# power_layout.net
KiCad netlist of a schematic drawn in EAGLE
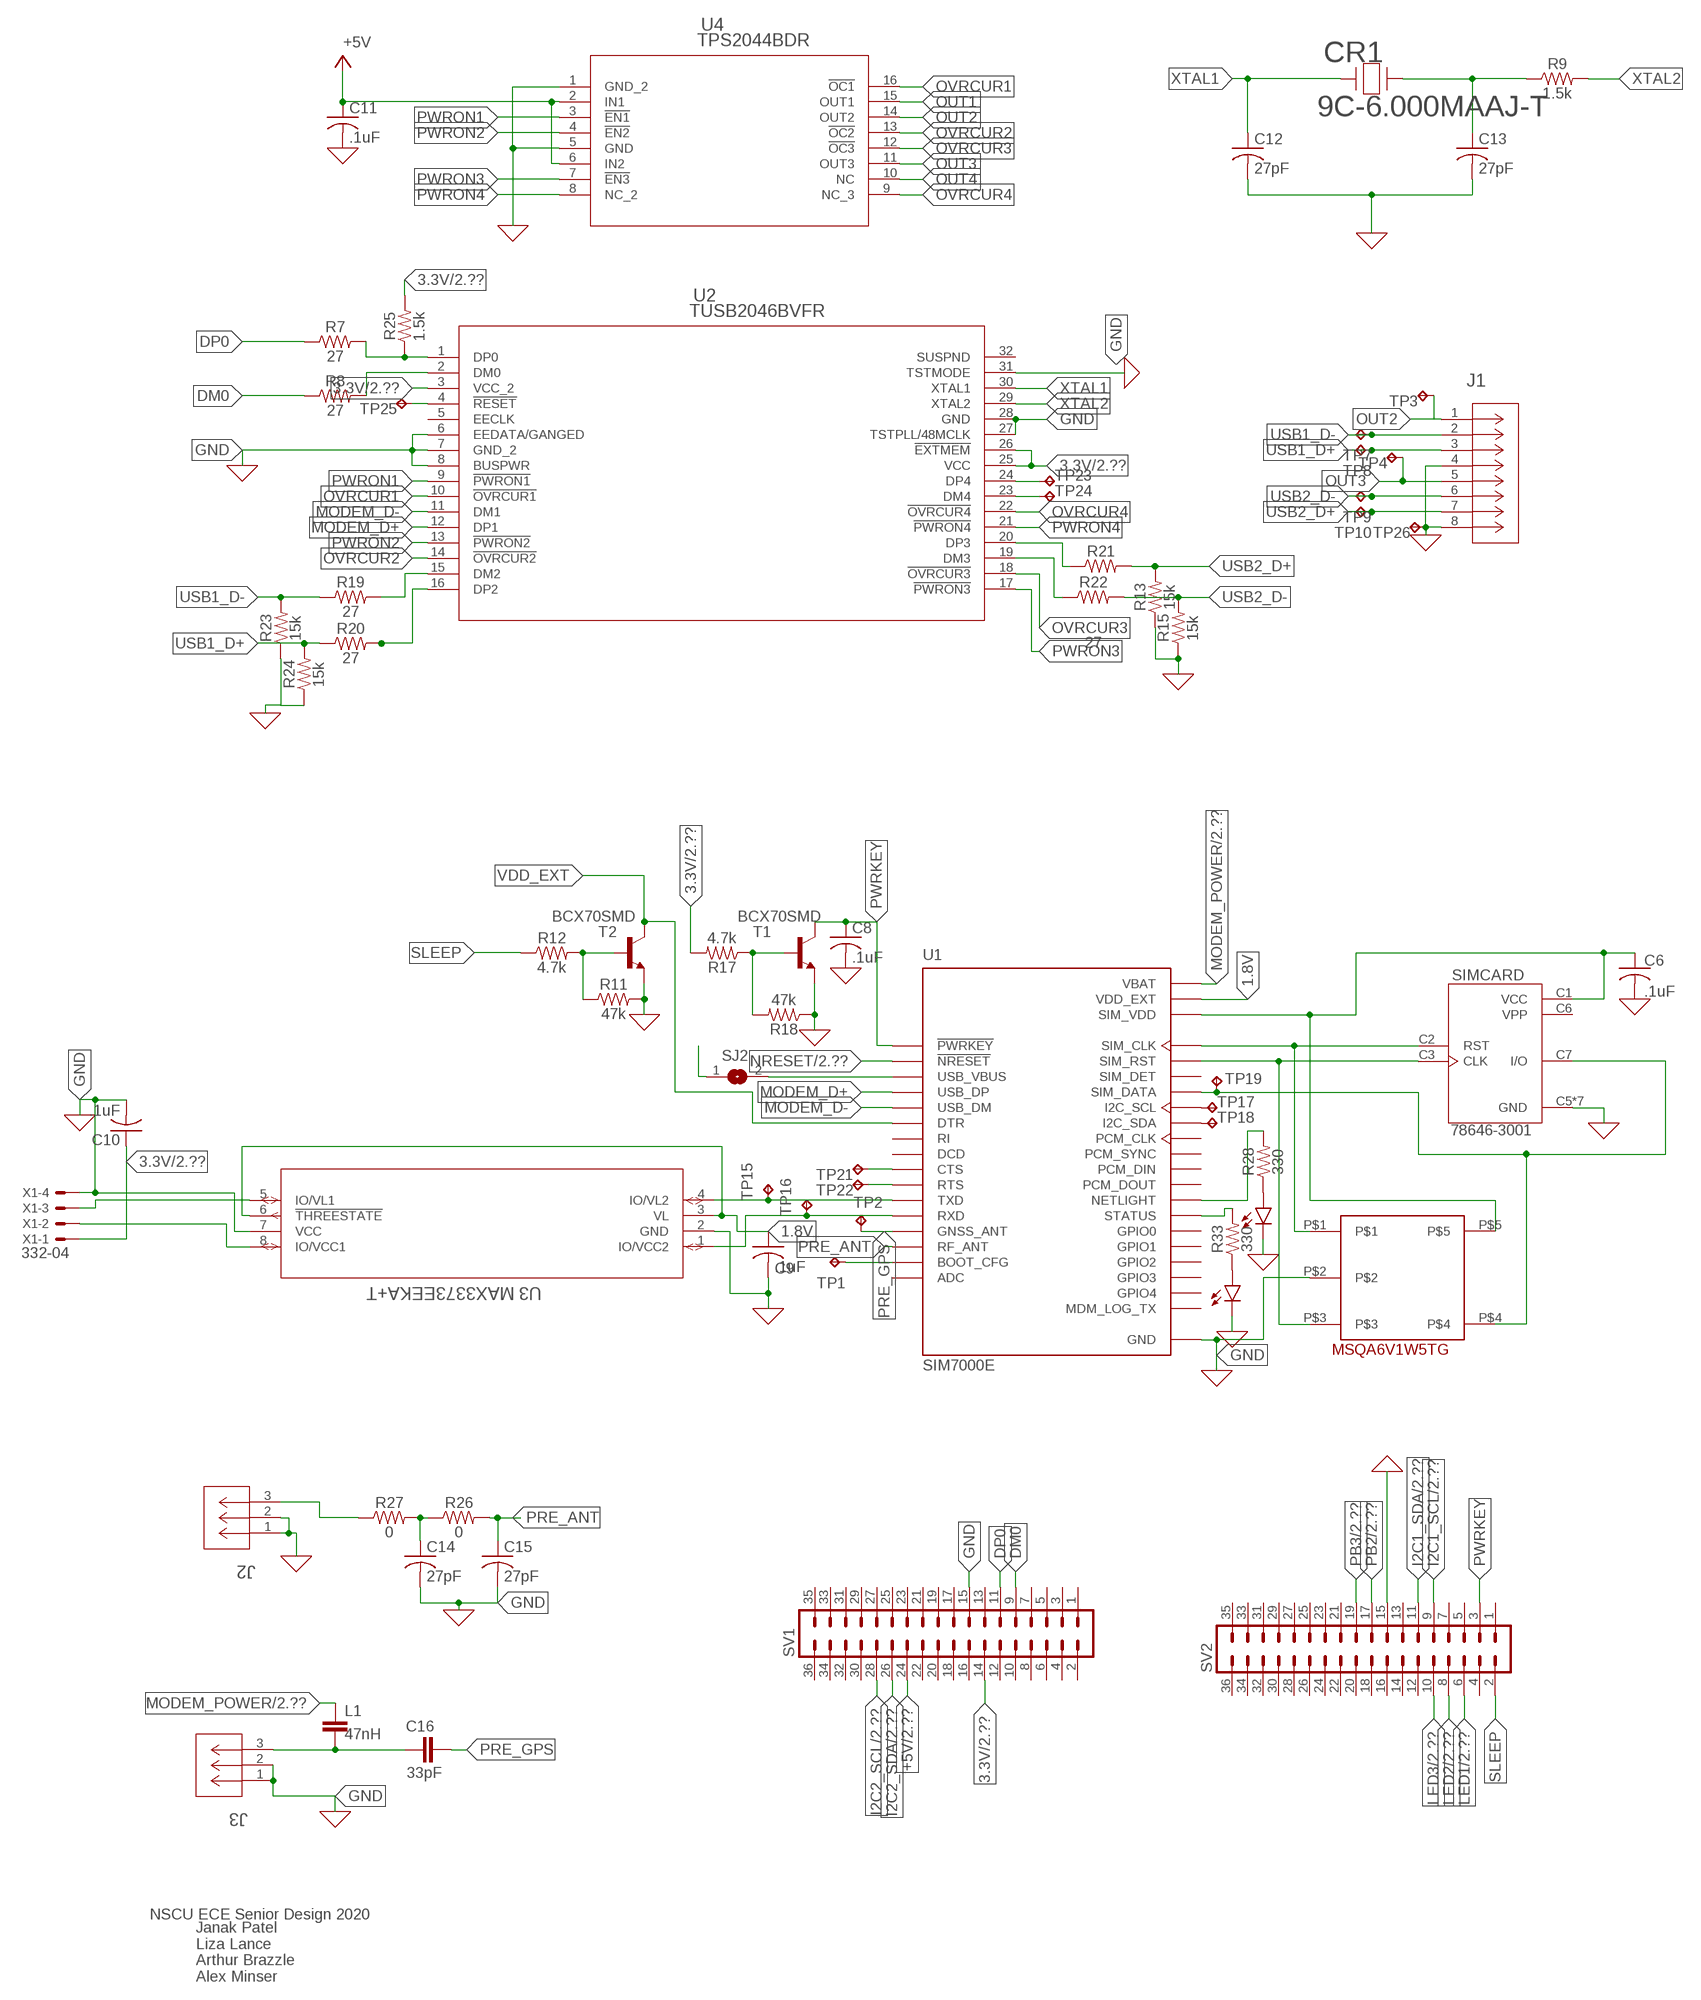
[diagram p0: schematic, sheet 1]
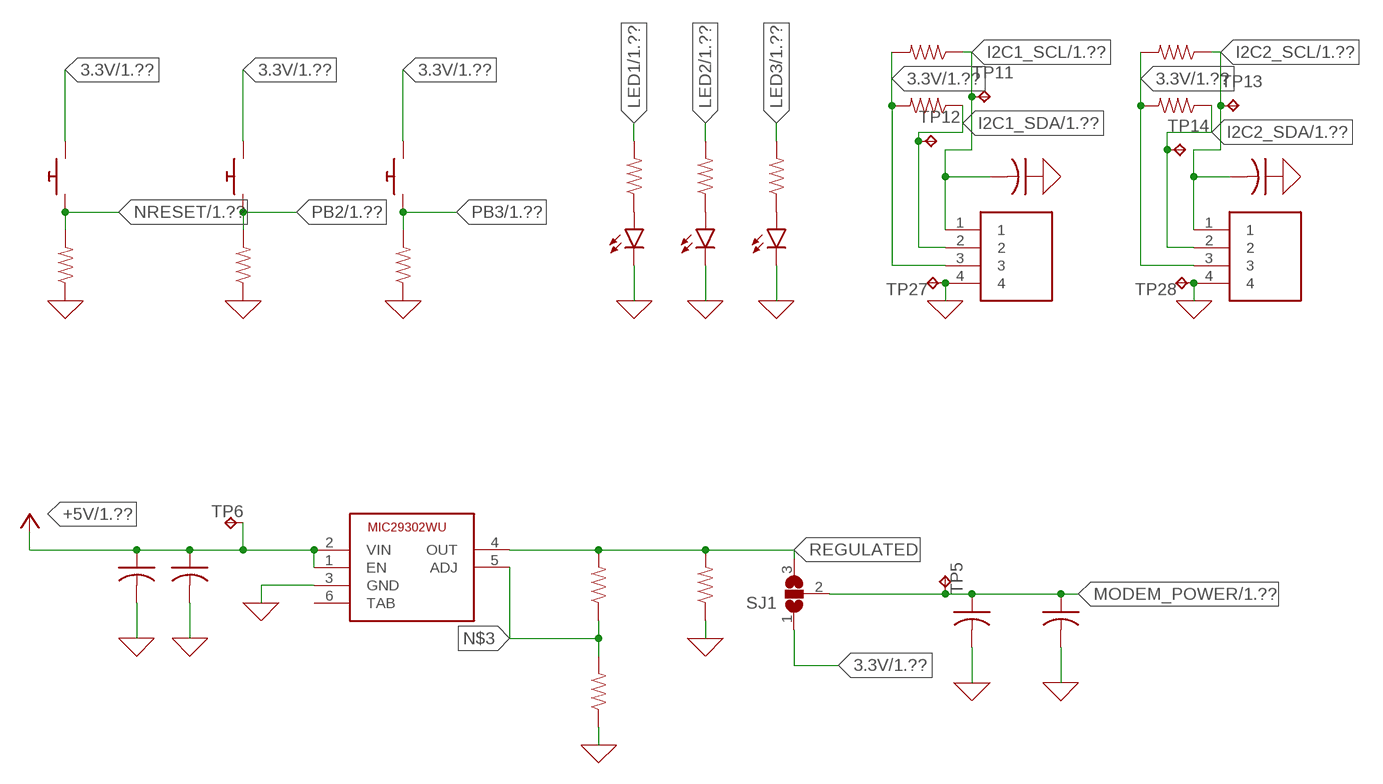
[diagram p1: schematic, sheet 2]

(export (version "E")
  (design (tool "Eeschema 10.0.6"))
  (components
    (comp (ref "C1")
      (value "100uF")
      (footprint "eagle-import:C0805")
      (libsource (lib "eagle-import") (part "C-USC0805"))
    )
    (comp (ref "C2")
      (value "0.1uF")
      (footprint "eagle-import:C0805")
      (libsource (lib "eagle-import") (part "C-USC0805"))
    )
    (comp (ref "C3")
      (value "330uF")
      (footprint "eagle-import:C1210")
      (libsource (lib "eagle-import") (part "C-USC1210"))
    )
    (comp (ref "C4")
      (value "1uF")
      (footprint "eagle-import:C0805")
      (libsource (lib "eagle-import") (part "C-USC0805"))
    )
    (comp (ref "C5")
      (value "100nF")
      (footprint "eagle-import:C0805")
      (libsource (lib "eagle-import") (part "C-USC0805"))
    )
    (comp (ref "C7")
      (value "0.1uF")
      (footprint "eagle-import:C0805")
      (libsource (lib "eagle-import") (part "C-USC0805"))
    )
    (comp (ref "D1")
      (value "RED")
      (footprint "eagle-import:LED-1206")
      (libsource (lib "eagle-import") (part "LED-RED1206"))
    )
    (comp (ref "D2")
      (value "GREEN")
      (footprint "eagle-import:LED-1206")
      (libsource (lib "eagle-import") (part "LED-GREEN1206"))
    )
    (comp (ref "D3")
      (value "BLUE")
      (footprint "eagle-import:LED-1206")
      (libsource (lib "eagle-import") (part "LED-BLUE1206"))
    )
    (comp (ref "GROVE1")
      (value "640456-4")
      (footprint "eagle-import:TE_640456-4")
      (fields (field (name "DIGI-KEY_PART_NUMBER") "A1922-ND") (field (name "MF") "TE Connectivity"))
      (libsource (lib "eagle-import") (part "640456-4"))
    )
    (comp (ref "GROVE2")
      (value "640456-4")
      (footprint "eagle-import:TE_640456-4")
      (fields (field (name "DIGI-KEY_PART_NUMBER") "A1922-ND") (field (name "MF") "TE Connectivity"))
      (libsource (lib "eagle-import") (part "640456-4"))
    )
    (comp (ref "POWER_SUPPLY")
      (value "MIC29302WU")
      (footprint "eagle-import:TO263-5")
      (fields (field (name "MF") "Microchip Technology"))
      (libsource (lib "eagle-import") (part "MIC29302WU"))
    )
    (comp (ref "R1")
      (value "60.4")
      (footprint "eagle-import:0805")
      (libsource (lib "eagle-import") (part "RESISTOR0805"))
    )
    (comp (ref "R2")
      (value "180")
      (footprint "eagle-import:0805")
      (libsource (lib "eagle-import") (part "RESISTOR0805"))
    )
    (comp (ref "R3")
      (value "180")
      (footprint "eagle-import:0805")
      (libsource (lib "eagle-import") (part "RESISTOR0805"))
    )
    (comp (ref "R4")
      (value "47k")
      (footprint "eagle-import:0805")
      (libsource (lib "eagle-import") (part "RESISTOR0805"))
    )
    (comp (ref "R5")
      (value "100k")
      (footprint "eagle-import:0805")
      (libsource (lib "eagle-import") (part "RESISTOR0805"))
    )
    (comp (ref "R6")
      (value "470k")
      (footprint "eagle-import:0805")
      (libsource (lib "eagle-import") (part "RESISTOR0805"))
    )
    (comp (ref "R10")
      (value "4700")
      (footprint "eagle-import:0805")
      (libsource (lib "eagle-import") (part "RESISTOR0805"))
    )
    (comp (ref "R14")
      (value "4700")
      (footprint "eagle-import:0805")
      (libsource (lib "eagle-import") (part "RESISTOR0805"))
    )
    (comp (ref "R16")
      (value "4700")
      (footprint "eagle-import:0805")
      (libsource (lib "eagle-import") (part "RESISTOR0805"))
    )
    (comp (ref "R29")
      (value "4700")
      (footprint "eagle-import:0805")
      (libsource (lib "eagle-import") (part "RESISTOR0805"))
    )
    (comp (ref "R30")
      (value "4700")
      (footprint "eagle-import:0805")
      (libsource (lib "eagle-import") (part "RESISTOR0805"))
    )
    (comp (ref "R31")
      (value "4700")
      (footprint "eagle-import:0805")
      (libsource (lib "eagle-import") (part "RESISTOR0805"))
    )
    (comp (ref "R32")
      (value "4700")
      (footprint "eagle-import:0805")
      (libsource (lib "eagle-import") (part "RESISTOR0805"))
    )
    (comp (ref "SJ1")
      (value "SJ2W")
      (footprint "eagle-import:SJ_2")
      (libsource (lib "eagle-import") (part "SJ2W"))
    )
    (comp (ref "SW1")
      (value "SWITCH_PUSHBUTTONSOFTTOUCHSMD_SJ")
      (footprint "eagle-import:PUSHBUTTON_SMD_SJ")
      (libsource (lib "eagle-import") (part "SWITCH_PUSHBUTTONSOFTTOUCHSMD_SJ"))
    )
    (comp (ref "SW2")
      (value "SWITCH_PUSHBUTTONSOFTTOUCHSMD_SJ")
      (footprint "eagle-import:PUSHBUTTON_SMD_SJ")
      (libsource (lib "eagle-import") (part "SWITCH_PUSHBUTTONSOFTTOUCHSMD_SJ"))
    )
    (comp (ref "SW3")
      (value "SWITCH_PUSHBUTTONSOFTTOUCHSMD_SJ")
      (footprint "eagle-import:PUSHBUTTON_SMD_SJ")
      (libsource (lib "eagle-import") (part "SWITCH_PUSHBUTTONSOFTTOUCHSMD_SJ"))
    )
    (comp (ref "TP5")
      (value "TPTP10R")
      (footprint "eagle-import:TP10R")
      (libsource (lib "eagle-import") (part "TPTP10R"))
    )
    (comp (ref "TP6")
      (value "TPTP10R")
      (footprint "eagle-import:TP10R")
      (libsource (lib "eagle-import") (part "TPTP10R"))
    )
    (comp (ref "TP11")
      (value "TPTP10R")
      (footprint "eagle-import:TP10R")
      (libsource (lib "eagle-import") (part "TPTP10R"))
    )
    (comp (ref "TP12")
      (value "TPTP10R")
      (footprint "eagle-import:TP10R")
      (libsource (lib "eagle-import") (part "TPTP10R"))
    )
    (comp (ref "TP13")
      (value "TPTP10R")
      (footprint "eagle-import:TP10R")
      (libsource (lib "eagle-import") (part "TPTP10R"))
    )
    (comp (ref "TP14")
      (value "TPTP10R")
      (footprint "eagle-import:TP10R")
      (libsource (lib "eagle-import") (part "TPTP10R"))
    )
    (comp (ref "TP27")
      (value "TPTP10R")
      (footprint "eagle-import:TP10R")
      (libsource (lib "eagle-import") (part "TPTP10R"))
    )
    (comp (ref "TP28")
      (value "TPTP10R")
      (footprint "eagle-import:TP10R")
      (libsource (lib "eagle-import") (part "TPTP10R"))
    )
    (comp (ref "C6")
      (value ".1uF")
      (footprint "eagle-import:C0805")
      (libsource (lib "eagle-import") (part "C-USC0805"))
    )
    (comp (ref "C8")
      (value ".1uF")
      (footprint "eagle-import:C0805")
      (libsource (lib "eagle-import") (part "C-USC0805"))
    )
    (comp (ref "C9")
      (value ".1uF")
      (footprint "eagle-import:C0805")
      (libsource (lib "eagle-import") (part "C-USC0805"))
    )
    (comp (ref "C10")
      (value ".1uF")
      (footprint "eagle-import:C0805")
      (libsource (lib "eagle-import") (part "C-USC0805"))
    )
    (comp (ref "C11")
      (value ".1uF")
      (footprint "eagle-import:C0805")
      (libsource (lib "eagle-import") (part "C-USC0805"))
    )
    (comp (ref "C12")
      (value "27pF")
      (footprint "eagle-import:C0603")
      (libsource (lib "eagle-import") (part "C-USC0603"))
    )
    (comp (ref "C13")
      (value "27pF")
      (footprint "eagle-import:C0603")
      (libsource (lib "eagle-import") (part "C-USC0603"))
    )
    (comp (ref "C14")
      (value "27pF")
      (footprint "eagle-import:C0603")
      (libsource (lib "eagle-import") (part "C-USC0603"))
    )
    (comp (ref "C15")
      (value "27pF")
      (footprint "eagle-import:C0603")
      (libsource (lib "eagle-import") (part "C-USC0603"))
    )
    (comp (ref "C16")
      (value "33pF")
      (footprint "eagle-import:C0603K")
      (libsource (lib "eagle-import") (part "C-EUC0603K"))
    )
    (comp (ref "CR1")
      (value "9C-6.000MAAJ-T")
      (footprint "eagle-import:CRYSTAL_TXC_9C_TXC")
      (libsource (lib "eagle-import") (part "9C-6.000MAAJ-T"))
    )
    (comp (ref "D4")
      (value "Yellow")
      (footprint "eagle-import:LED-0603")
      (libsource (lib "eagle-import") (part "LED-YELLOW0603"))
    )
    (comp (ref "D5")
      (value "Yellow")
      (footprint "eagle-import:LED-0603")
      (libsource (lib "eagle-import") (part "LED-YELLOW0603"))
    )
    (comp (ref "J1")
      (value "AU-Y1008-2")
      (footprint "eagle-import:CONN_AU-Y1008-2_ASM")
      (fields (field (name "COPYRIGHT") "Copyright (C) 2018 Accelerated Designs. All rights reserved"))
      (libsource (lib "eagle-import") (part "AU-Y1008-2"))
    )
    (comp (ref "J2")
      (value "U.FL-R-SMT-1(01)")
      (footprint "eagle-import:CONN_-SMT-1(01)")
      (fields (field (name "COPYRIGHT") "Copyright (C) 2018 Accelerated Designs. All rights reserved"))
      (libsource (lib "eagle-import") (part "U.FL-R-SMT-1(01)"))
    )
    (comp (ref "J3")
      (value "U.FL-R-SMT-1(01)")
      (footprint "eagle-import:CONN_-SMT-1(01)")
      (fields (field (name "COPYRIGHT") "Copyright (C) 2018 Accelerated Designs. All rights reserved"))
      (libsource (lib "eagle-import") (part "U.FL-R-SMT-1(01)"))
    )
    (comp (ref "L1")
      (value "47nH")
      (footprint "eagle-import:C1608")
      (libsource (lib "eagle-import") (part "C-EUC1608"))
    )
    (comp (ref "R7")
      (value "27")
      (footprint "eagle-import:0805")
      (libsource (lib "eagle-import") (part "RESISTOR0805"))
    )
    (comp (ref "R8")
      (value "27")
      (footprint "eagle-import:0805")
      (libsource (lib "eagle-import") (part "RESISTOR0805"))
    )
    (comp (ref "R9")
      (value "1.5k")
      (footprint "eagle-import:0603")
      (libsource (lib "eagle-import") (part "1KOHM-0603-1/10W-1%"))
    )
    (comp (ref "R11")
      (value "47k")
      (footprint "eagle-import:0603")
      (libsource (lib "eagle-import") (part "47KOHM-0603-1/10W-1%"))
    )
    (comp (ref "R12")
      (value "4.7k")
      (footprint "eagle-import:0603")
      (libsource (lib "eagle-import") (part "4.7KOHM-0603-1/10W-1%"))
    )
    (comp (ref "R13")
      (value "15k")
      (footprint "eagle-import:0805")
      (libsource (lib "eagle-import") (part "RESISTOR0805"))
    )
    (comp (ref "R15")
      (value "15k")
      (footprint "eagle-import:0805")
      (libsource (lib "eagle-import") (part "RESISTOR0805"))
    )
    (comp (ref "R17")
      (value "4.7k")
      (footprint "eagle-import:0603")
      (libsource (lib "eagle-import") (part "4.7KOHM-0603-1/10W-1%"))
    )
    (comp (ref "R18")
      (value "47k")
      (footprint "eagle-import:0603")
      (libsource (lib "eagle-import") (part "47KOHM-0603-1/10W-1%"))
    )
    (comp (ref "R19")
      (value "27")
      (footprint "eagle-import:0805")
      (libsource (lib "eagle-import") (part "RESISTOR0805"))
    )
    (comp (ref "R20")
      (value "27")
      (footprint "eagle-import:0805")
      (libsource (lib "eagle-import") (part "RESISTOR0805"))
    )
    (comp (ref "R21")
      (value "27")
      (footprint "eagle-import:0805")
      (libsource (lib "eagle-import") (part "RESISTOR0805"))
    )
    (comp (ref "R22")
      (value "27")
      (footprint "eagle-import:0805")
      (libsource (lib "eagle-import") (part "RESISTOR0805"))
    )
    (comp (ref "R23")
      (value "15k")
      (footprint "eagle-import:0805")
      (libsource (lib "eagle-import") (part "RESISTOR0805"))
    )
    (comp (ref "R24")
      (value "15k")
      (footprint "eagle-import:0805")
      (libsource (lib "eagle-import") (part "RESISTOR0805"))
    )
    (comp (ref "R25")
      (value "1.5k")
      (footprint "eagle-import:0805")
      (libsource (lib "eagle-import") (part "RESISTOR0805"))
    )
    (comp (ref "R26")
      (value "0")
      (footprint "eagle-import:0603")
      (libsource (lib "eagle-import") (part "1KOHM-0603-1/10W-1%"))
    )
    (comp (ref "R27")
      (value "0")
      (footprint "eagle-import:0603")
      (libsource (lib "eagle-import") (part "1KOHM-0603-1/10W-1%"))
    )
    (comp (ref "R28")
      (value "330")
      (footprint "eagle-import:0603")
      (libsource (lib "eagle-import") (part "1KOHM-0603-1/10W-1%"))
    )
    (comp (ref "R33")
      (value "330")
      (footprint "eagle-import:0603")
      (libsource (lib "eagle-import") (part "1KOHM-0603-1/10W-1%"))
    )
    (comp (ref "SIMCARD")
      (value "78646-3001")
      (footprint "eagle-import:MOLEX_78646-3001")
      (fields (field (name "MF") "Molex"))
      (libsource (lib "eagle-import") (part "78646-3001"))
    )
    (comp (ref "SJ2") (value "SJ") (footprint "eagle-import:SJ") (libsource (lib "eagle-import") (part "SJ")))
    (comp (ref "SV1")
      (value "MA18-2")
      (footprint "eagle-import:MA18-2")
      (libsource (lib "eagle-import") (part "MA18-2"))
    )
    (comp (ref "SV2")
      (value "MA18-2")
      (footprint "eagle-import:MA18-2")
      (libsource (lib "eagle-import") (part "MA18-2"))
    )
    (comp (ref "T1")
      (value "BCX70SMD")
      (footprint "eagle-import:SOT23")
      (libsource (lib "eagle-import") (part "BCX70SMD"))
    )
    (comp (ref "T2")
      (value "BCX70SMD")
      (footprint "eagle-import:SOT23")
      (libsource (lib "eagle-import") (part "BCX70SMD"))
    )
    (comp (ref "TP1")
      (value "TPTP10R")
      (footprint "eagle-import:TP10R")
      (libsource (lib "eagle-import") (part "TPTP10R"))
    )
    (comp (ref "TP2")
      (value "TPTP16R")
      (footprint "eagle-import:TP16R")
      (libsource (lib "eagle-import") (part "TPTP16R"))
    )
    (comp (ref "TP3")
      (value "TPTP10R")
      (footprint "eagle-import:TP10R")
      (libsource (lib "eagle-import") (part "TPTP10R"))
    )
    (comp (ref "TP4")
      (value "TPTP10R")
      (footprint "eagle-import:TP10R")
      (libsource (lib "eagle-import") (part "TPTP10R"))
    )
    (comp (ref "TP7")
      (value "TPTP10R")
      (footprint "eagle-import:TP10R")
      (libsource (lib "eagle-import") (part "TPTP10R"))
    )
    (comp (ref "TP8")
      (value "TPTP10R")
      (footprint "eagle-import:TP10R")
      (libsource (lib "eagle-import") (part "TPTP10R"))
    )
    (comp (ref "TP9")
      (value "TPTP10R")
      (footprint "eagle-import:TP10R")
      (libsource (lib "eagle-import") (part "TPTP10R"))
    )
    (comp (ref "TP10")
      (value "TPTP10R")
      (footprint "eagle-import:TP10R")
      (libsource (lib "eagle-import") (part "TPTP10R"))
    )
    (comp (ref "TP15")
      (value "TPTP10R")
      (footprint "eagle-import:TP10R")
      (libsource (lib "eagle-import") (part "TPTP10R"))
    )
    (comp (ref "TP16")
      (value "TPTP10R")
      (footprint "eagle-import:TP10R")
      (libsource (lib "eagle-import") (part "TPTP10R"))
    )
    (comp (ref "TP17")
      (value "TPTP10R")
      (footprint "eagle-import:TP10R")
      (libsource (lib "eagle-import") (part "TPTP10R"))
    )
    (comp (ref "TP18")
      (value "TPTP10R")
      (footprint "eagle-import:TP10R")
      (libsource (lib "eagle-import") (part "TPTP10R"))
    )
    (comp (ref "TP19")
      (value "TPTP10R")
      (footprint "eagle-import:TP10R")
      (libsource (lib "eagle-import") (part "TPTP10R"))
    )
    (comp (ref "TP21")
      (value "TPTP10R")
      (footprint "eagle-import:TP10R")
      (libsource (lib "eagle-import") (part "TPTP10R"))
    )
    (comp (ref "TP22")
      (value "TPTP10R")
      (footprint "eagle-import:TP10R")
      (libsource (lib "eagle-import") (part "TPTP10R"))
    )
    (comp (ref "TP23")
      (value "TPTP10R")
      (footprint "eagle-import:TP10R")
      (libsource (lib "eagle-import") (part "TPTP10R"))
    )
    (comp (ref "TP24")
      (value "TPTP10R")
      (footprint "eagle-import:TP10R")
      (libsource (lib "eagle-import") (part "TPTP10R"))
    )
    (comp (ref "TP25")
      (value "TPTP10R")
      (footprint "eagle-import:TP10R")
      (libsource (lib "eagle-import") (part "TPTP10R"))
    )
    (comp (ref "TP26")
      (value "TPTP10R")
      (footprint "eagle-import:TP10R")
      (libsource (lib "eagle-import") (part "TPTP10R"))
    )
    (comp (ref "U1")
      (value "SIM7000E")
      (footprint "eagle-import:SIMCON_SIM7000E")
      (fields (field (name "MF") "DFRobot"))
      (libsource (lib "eagle-import") (part "SIM7000E"))
    )
    (comp (ref "U2")
      (value "TUSB2046BVFR")
      (footprint "eagle-import:VF32_TEX")
      (fields
        (field (name "MANUFACTURER") "Texas Instruments")
        (field (name "COPYRIGHT") "Copyright (C) 2018 Accelerated Designs. All rights reserved")
      )
      (libsource (lib "eagle-import") (part "TUSB2046BVFR"))
    )
    (comp (ref "U3")
      (value "MAX3373EEKA+T")
      (footprint "eagle-import:21-0078H")
      (fields (field (name "MANUFACTURER_PART_NUMBER") "max3373eeka+t"))
      (libsource (lib "eagle-import") (part "MAX3373EEKA+T"))
    )
    (comp (ref "U4")
      (value "TPS2044BDR")
      (footprint "eagle-import:D16_TEX")
      (fields (field (name "MANUFACTURER") "Texas Instruments"))
      (libsource (lib "eagle-import") (part "TPS2044BDR"))
    )
    (comp (ref "U5")
      (value "MSQA6V1W5T2G")
      (footprint "eagle-import:SOT-23-5_M5")
      (libsource (lib "eagle-import") (part "MSQA6V1W5T2G"))
    )
    (comp (ref "X1")
      (value "332-04")
      (footprint "eagle-import:332-04")
      (libsource (lib "eagle-import") (part "332-04"))
    )
  )
  (nets
    (net (code "1") (name "+5V") (class "Default")
      (node (ref "C1") (pin "1") (pinfunction "1_1") (pintype "passive"))
      (node (ref "C11") (pin "1") (pinfunction "1_1") (pintype "passive"))
      (node (ref "C4") (pin "1") (pinfunction "1_1") (pintype "passive"))
      (node (ref "POWER_SUPPLY") (pin "1") (pinfunction "EN_1") (pintype "bidirectional"))
      (node (ref "POWER_SUPPLY") (pin "2") (pinfunction "VIN_2") (pintype "bidirectional"))
      (node (ref "SJ2") (pin "1") (pinfunction "1_1") (pintype "passive"))
      (node (ref "SV1") (pin "24") (pinfunction "24_24") (pintype "passive"))
      (node (ref "TP6") (pin "TP") (pinfunction "TP_TP") (pintype "input"))
      (node (ref "U4") (pin "2") (pinfunction "IN1_2") (pintype "input"))
      (node (ref "U4") (pin "6") (pinfunction "IN2_6") (pintype "input"))
    )
    (net (code "2") (name "1.8V") (class "Default")
      (node (ref "C9") (pin "1") (pinfunction "1_1") (pintype "passive"))
      (node (ref "U1") (pin "15") (pinfunction "VDD_EXT_15") (pintype "power_in"))
      (node (ref "U3") (pin "3") (pinfunction "VL_3") (pintype "power_in"))
      (node (ref "U3") (pin "6") (pinfunction "~{THREESTATE}_6") (pintype "output"))
    )
    (net (code "3") (name "3.3V") (class "Default")
      (node (ref "C10") (pin "1") (pinfunction "1_1") (pintype "passive"))
      (node (ref "GROVE1") (pin "3") (pinfunction "3_3") (pintype "passive"))
      (node (ref "GROVE2") (pin "3") (pinfunction "3_3") (pintype "passive"))
      (node (ref "R17") (pin "2") (pinfunction "2_2") (pintype "passive"))
      (node (ref "R25") (pin "2") (pinfunction "2_2") (pintype "passive"))
      (node (ref "R29") (pin "2") (pinfunction "2_2") (pintype "passive"))
      (node (ref "R30") (pin "2") (pinfunction "2_2") (pintype "passive"))
      (node (ref "R31") (pin "2") (pinfunction "2_2") (pintype "passive"))
      (node (ref "R32") (pin "2") (pinfunction "2_2") (pintype "passive"))
      (node (ref "SJ1") (pin "1") (pinfunction "1_1") (pintype "passive"))
      (node (ref "SV1") (pin "14") (pinfunction "14_14") (pintype "passive"))
      (node (ref "SW1") (pin "P$2") (pinfunction "P$2_P$2") (pintype "passive"))
      (node (ref "SW2") (pin "P$2") (pinfunction "P$2_P$2") (pintype "passive"))
      (node (ref "SW3") (pin "P$2") (pinfunction "P$2_P$2") (pintype "passive"))
      (node (ref "U2") (pin "25") (pinfunction "VCC_25") (pintype "power_in"))
      (node (ref "U2") (pin "26") (pinfunction "~{EXTMEM}_26") (pintype "input"))
      (node (ref "U2") (pin "3") (pinfunction "VCC_2_3") (pintype "power_in"))
      (node (ref "X1") (pin "1") (pinfunction "S_1") (pintype "passive"))
    )
    (net (code "4") (name "DM0") (class "Default")
      (node (ref "R8") (pin "1") (pinfunction "1_1") (pintype "passive"))
      (node (ref "SV1") (pin "9") (pinfunction "9_9") (pintype "passive"))
    )
    (net (code "5") (name "DP0") (class "Default")
      (node (ref "R7") (pin "1") (pinfunction "1_1") (pintype "passive"))
      (node (ref "SV1") (pin "11") (pinfunction "11_11") (pintype "passive"))
    )
    (net (code "6") (name "GND") (class "Default")
      (node (ref "C1") (pin "2") (pinfunction "2_2") (pintype "passive"))
      (node (ref "C10") (pin "2") (pinfunction "2_2") (pintype "passive"))
      (node (ref "C11") (pin "2") (pinfunction "2_2") (pintype "passive"))
      (node (ref "C12") (pin "2") (pinfunction "2_2") (pintype "passive"))
      (node (ref "C13") (pin "2") (pinfunction "2_2") (pintype "passive"))
      (node (ref "C14") (pin "2") (pinfunction "2_2") (pintype "passive"))
      (node (ref "C15") (pin "2") (pinfunction "2_2") (pintype "passive"))
      (node (ref "C2") (pin "1") (pinfunction "1_1") (pintype "passive"))
      (node (ref "C3") (pin "2") (pinfunction "2_2") (pintype "passive"))
      (node (ref "C4") (pin "2") (pinfunction "2_2") (pintype "passive"))
      (node (ref "C5") (pin "2") (pinfunction "2_2") (pintype "passive"))
      (node (ref "C6") (pin "2") (pinfunction "2_2") (pintype "passive"))
      (node (ref "C7") (pin "1") (pinfunction "1_1") (pintype "passive"))
      (node (ref "C8") (pin "2") (pinfunction "2_2") (pintype "passive"))
      (node (ref "C9") (pin "2") (pinfunction "2_2") (pintype "passive"))
      (node (ref "D1") (pin "C") (pinfunction "C_C") (pintype "passive"))
      (node (ref "D2") (pin "C") (pinfunction "C_C") (pintype "passive"))
      (node (ref "D3") (pin "C") (pinfunction "C_C") (pintype "passive"))
      (node (ref "D4") (pin "C") (pinfunction "C_C") (pintype "passive"))
      (node (ref "D5") (pin "C") (pinfunction "C_C") (pintype "passive"))
      (node (ref "GROVE1") (pin "4") (pinfunction "4_4") (pintype "passive"))
      (node (ref "GROVE2") (pin "4") (pinfunction "4_4") (pintype "passive"))
      (node (ref "J1") (pin "4") (pinfunction "4_4") (pintype "passive"))
      (node (ref "J1") (pin "8") (pinfunction "8_8") (pintype "passive"))
      (node (ref "J2") (pin "1") (pinfunction "1_1") (pintype "passive"))
      (node (ref "J2") (pin "2") (pinfunction "2_2") (pintype "passive"))
      (node (ref "J3") (pin "1") (pinfunction "1_1") (pintype "passive"))
      (node (ref "J3") (pin "2") (pinfunction "2_2") (pintype "passive"))
      (node (ref "POWER_SUPPLY") (pin "3") (pinfunction "GND_3") (pintype "bidirectional"))
      (node (ref "R10") (pin "1") (pinfunction "1_1") (pintype "passive"))
      (node (ref "R11") (pin "2") (pinfunction "2_2") (pintype "passive"))
      (node (ref "R13") (pin "1") (pinfunction "1_1") (pintype "passive"))
      (node (ref "R14") (pin "1") (pinfunction "1_1") (pintype "passive"))
      (node (ref "R15") (pin "1") (pinfunction "1_1") (pintype "passive"))
      (node (ref "R16") (pin "1") (pinfunction "1_1") (pintype "passive"))
      (node (ref "R18") (pin "1") (pinfunction "1_1") (pintype "passive"))
      (node (ref "R23") (pin "1") (pinfunction "1_1") (pintype "passive"))
      (node (ref "R24") (pin "1") (pinfunction "1_1") (pintype "passive"))
      (node (ref "R4") (pin "1") (pinfunction "1_1") (pintype "passive"))
      (node (ref "R6") (pin "1") (pinfunction "1_1") (pintype "passive"))
      (node (ref "SIMCARD") (pin "C5") (pinfunction "GND_C5") (pintype "power_in"))
      (node (ref "SIMCARD") (pin "G1") (pinfunction "GND_G1") (pintype "power_in"))
      (node (ref "SIMCARD") (pin "G2") (pinfunction "GND_G2") (pintype "power_in"))
      (node (ref "SIMCARD") (pin "G3") (pinfunction "GND_G3") (pintype "power_in"))
      (node (ref "SIMCARD") (pin "G4") (pinfunction "GND_G4") (pintype "power_in"))
      (node (ref "SIMCARD") (pin "G5") (pinfunction "GND_G5") (pintype "power_in"))
      (node (ref "SIMCARD") (pin "G6") (pinfunction "GND_G6") (pintype "power_in"))
      (node (ref "SV1") (pin "15") (pinfunction "15_15") (pintype "passive"))
      (node (ref "SV2") (pin "15") (pinfunction "15_15") (pintype "passive"))
      (node (ref "T1") (pin "2") (pinfunction "E_2") (pintype "passive"))
      (node (ref "T2") (pin "2") (pinfunction "E_2") (pintype "passive"))
      (node (ref "TP26") (pin "TP") (pinfunction "TP_TP") (pintype "input"))
      (node (ref "TP27") (pin "TP") (pinfunction "TP_TP") (pintype "input"))
      (node (ref "TP28") (pin "TP") (pinfunction "TP_TP") (pintype "input"))
      (node (ref "U1") (pin "17") (pinfunction "GND_17") (pintype "power_in"))
      (node (ref "U1") (pin "18") (pinfunction "GND_18") (pintype "power_in"))
      (node (ref "U1") (pin "2") (pinfunction "GND_2") (pintype "power_in"))
      (node (ref "U1") (pin "29") (pinfunction "GND_29") (pintype "power_in"))
      (node (ref "U1") (pin "39") (pinfunction "GND_39") (pintype "power_in"))
      (node (ref "U1") (pin "45") (pinfunction "GND_45") (pintype "power_in"))
      (node (ref "U1") (pin "46") (pinfunction "GND_46") (pintype "power_in"))
      (node (ref "U1") (pin "54") (pinfunction "GND_54") (pintype "power_in"))
      (node (ref "U1") (pin "58") (pinfunction "GND_58") (pintype "power_in"))
      (node (ref "U1") (pin "59") (pinfunction "GND_59") (pintype "power_in"))
      (node (ref "U1") (pin "61") (pinfunction "GND_61") (pintype "power_in"))
      (node (ref "U1") (pin "62") (pinfunction "GND_62") (pintype "power_in"))
      (node (ref "U1") (pin "63") (pinfunction "GND_63") (pintype "power_in"))
      (node (ref "U1") (pin "64") (pinfunction "GND_64") (pintype "power_in"))
      (node (ref "U1") (pin "65") (pinfunction "GND_65") (pintype "power_in"))
      (node (ref "U2") (pin "27") (pinfunction "TSTPLL/48MCLK_27") (pintype "passive"))
      (node (ref "U2") (pin "28") (pinfunction "GND_28") (pintype "power_in"))
      (node (ref "U2") (pin "31") (pinfunction "TSTMODE_31") (pintype "passive"))
      (node (ref "U2") (pin "6") (pinfunction "EEDATA/GANGED_6") (pintype "bidirectional"))
      (node (ref "U2") (pin "7") (pinfunction "GND_2_7") (pintype "power_in"))
      (node (ref "U2") (pin "8") (pinfunction "BUSPWR_8") (pintype "input"))
      (node (ref "U3") (pin "2") (pinfunction "GND_2") (pintype "power_in"))
      (node (ref "U3") (pin "7") (pinfunction "VCC_7") (pintype "power_in"))
      (node (ref "U4") (pin "1") (pinfunction "GND_2_1") (pintype "power_in"))
      (node (ref "U4") (pin "5") (pinfunction "GND_5") (pintype "power_in"))
      (node (ref "U5") (pin "P$2") (pinfunction "P$2_P$2") (pintype "bidirectional"))
      (node (ref "X1") (pin "4") (pinfunction "S_4") (pintype "passive"))
    )
    (net (code "7") (name "I2C1_SCL") (class "Default")
      (node (ref "C2") (pin "2") (pinfunction "2_2") (pintype "passive"))
      (node (ref "GROVE1") (pin "1") (pinfunction "1_1") (pintype "passive"))
      (node (ref "R29") (pin "1") (pinfunction "1_1") (pintype "passive"))
      (node (ref "SV2") (pin "9") (pinfunction "9_9") (pintype "passive"))
      (node (ref "TP11") (pin "TP") (pinfunction "TP_TP") (pintype "input"))
    )
    (net (code "8") (name "I2C1_SDA") (class "Default")
      (node (ref "GROVE1") (pin "2") (pinfunction "2_2") (pintype "passive"))
      (node (ref "R30") (pin "1") (pinfunction "1_1") (pintype "passive"))
      (node (ref "SV2") (pin "11") (pinfunction "11_11") (pintype "passive"))
      (node (ref "TP12") (pin "TP") (pinfunction "TP_TP") (pintype "input"))
    )
    (net (code "9") (name "I2C2_SCL") (class "Default")
      (node (ref "C7") (pin "2") (pinfunction "2_2") (pintype "passive"))
      (node (ref "GROVE2") (pin "1") (pinfunction "1_1") (pintype "passive"))
      (node (ref "R31") (pin "1") (pinfunction "1_1") (pintype "passive"))
      (node (ref "SV1") (pin "28") (pinfunction "28_28") (pintype "passive"))
      (node (ref "TP13") (pin "TP") (pinfunction "TP_TP") (pintype "input"))
    )
    (net (code "10") (name "I2C2_SDA") (class "Default")
      (node (ref "GROVE2") (pin "2") (pinfunction "2_2") (pintype "passive"))
      (node (ref "R32") (pin "1") (pinfunction "1_1") (pintype "passive"))
      (node (ref "SV1") (pin "26") (pinfunction "26_26") (pintype "passive"))
      (node (ref "TP14") (pin "TP") (pinfunction "TP_TP") (pintype "input"))
    )
    (net (code "11") (name "LED1") (class "Default")
      (node (ref "R3") (pin "2") (pinfunction "2_2") (pintype "passive"))
      (node (ref "SV2") (pin "6") (pinfunction "6_6") (pintype "passive"))
    )
    (net (code "12") (name "LED2") (class "Default")
      (node (ref "R2") (pin "2") (pinfunction "2_2") (pintype "passive"))
      (node (ref "SV2") (pin "8") (pinfunction "8_8") (pintype "passive"))
    )
    (net (code "13") (name "LED3") (class "Default")
      (node (ref "R1") (pin "2") (pinfunction "2_2") (pintype "passive"))
      (node (ref "SV2") (pin "10") (pinfunction "10_10") (pintype "passive"))
    )
    (net (code "14") (name "MODEM_D+") (class "Default")
      (node (ref "U1") (pin "27") (pinfunction "USB_DP_27") (pintype "bidirectional"))
      (node (ref "U2") (pin "12") (pinfunction "DP1_12") (pintype "bidirectional"))
    )
    (net (code "15") (name "MODEM_D-") (class "Default")
      (node (ref "U1") (pin "28") (pinfunction "USB_DM_28") (pintype "bidirectional"))
      (node (ref "U2") (pin "11") (pinfunction "DM1_11") (pintype "bidirectional"))
    )
    (net (code "16") (name "MODEM_POWER") (class "Default")
      (node (ref "C3") (pin "1") (pinfunction "1_1") (pintype "passive"))
      (node (ref "C5") (pin "1") (pinfunction "1_1") (pintype "passive"))
      (node (ref "L1") (pin "1") (pinfunction "1_1") (pintype "passive"))
      (node (ref "SJ1") (pin "2") (pinfunction "2_2") (pintype "passive"))
      (node (ref "TP5") (pin "TP") (pinfunction "TP_TP") (pintype "input"))
      (node (ref "U1") (pin "55") (pinfunction "VBAT_55") (pintype "power_in"))
      (node (ref "U1") (pin "56") (pinfunction "VBAT_56") (pintype "power_in"))
      (node (ref "U1") (pin "57") (pinfunction "VBAT_57") (pintype "power_in"))
    )
    (net (code "17") (name "N$3") (class "Default")
      (node (ref "POWER_SUPPLY") (pin "5") (pinfunction "ADJ_5") (pintype "bidirectional"))
      (node (ref "R4") (pin "2") (pinfunction "2_2") (pintype "passive"))
      (node (ref "R5") (pin "1") (pinfunction "1_1") (pintype "passive"))
    )
    (net (code "18") (name "NRESET") (class "Default")
      (node (ref "R10") (pin "2") (pinfunction "2_2") (pintype "passive"))
      (node (ref "SW1") (pin "P$1") (pinfunction "P$1_P$1") (pintype "passive"))
      (node (ref "U1") (pin "16") (pinfunction "~{NRESET}_16") (pintype "input"))
    )
    (net (code "19") (name "Net-(C13-Pad1)") (class "Default")
      (node (ref "C13") (pin "1") (pinfunction "1_1") (pintype "passive"))
      (node (ref "CR1") (pin "2") (pinfunction "2_2") (pintype "passive"))
      (node (ref "R9") (pin "1") (pinfunction "1_1") (pintype "passive"))
    )
    (net (code "20") (name "Net-(C14-Pad1)") (class "Default")
      (node (ref "C14") (pin "1") (pinfunction "1_1") (pintype "passive"))
      (node (ref "R26") (pin "1") (pinfunction "1_1") (pintype "passive"))
      (node (ref "R27") (pin "2") (pinfunction "2_2") (pintype "passive"))
    )
    (net (code "21") (name "Net-(C16-Pad1)") (class "Default")
      (node (ref "C16") (pin "1") (pinfunction "1_1") (pintype "passive"))
      (node (ref "J3") (pin "3") (pinfunction "3_3") (pintype "passive"))
      (node (ref "L1") (pin "2") (pinfunction "2_2") (pintype "passive"))
    )
    (net (code "22") (name "Net-(D1-PadA)") (class "Default")
      (node (ref "D1") (pin "A") (pinfunction "A_A") (pintype "passive"))
      (node (ref "R3") (pin "1") (pinfunction "1_1") (pintype "passive"))
    )
    (net (code "23") (name "Net-(D2-PadA)") (class "Default")
      (node (ref "D2") (pin "A") (pinfunction "A_A") (pintype "passive"))
      (node (ref "R2") (pin "1") (pinfunction "1_1") (pintype "passive"))
    )
    (net (code "24") (name "Net-(D3-PadA)") (class "Default")
      (node (ref "D3") (pin "A") (pinfunction "A_A") (pintype "passive"))
      (node (ref "R1") (pin "1") (pinfunction "1_1") (pintype "passive"))
    )
    (net (code "25") (name "Net-(D4-PadA)") (class "Default")
      (node (ref "D4") (pin "A") (pinfunction "A_A") (pintype "passive"))
      (node (ref "R28") (pin "1") (pinfunction "1_1") (pintype "passive"))
    )
    (net (code "26") (name "Net-(D5-PadA)") (class "Default")
      (node (ref "D5") (pin "A") (pinfunction "A_A") (pintype "passive"))
      (node (ref "R33") (pin "1") (pinfunction "1_1") (pintype "passive"))
    )
    (net (code "27") (name "Net-(J2-Pad3)") (class "Default")
      (node (ref "J2") (pin "3") (pinfunction "3_3") (pintype "passive"))
      (node (ref "R27") (pin "1") (pinfunction "1_1") (pintype "passive"))
    )
    (net (code "28") (name "Net-(SIMCARD-CLK)") (class "Default")
      (node (ref "SIMCARD") (pin "C3") (pinfunction "CLK_C3") (pintype "input"))
      (node (ref "U1") (pin "33") (pinfunction "SIM_RST_33") (pintype "output"))
      (node (ref "U5") (pin "P$3") (pinfunction "P$3_P$3") (pintype "bidirectional"))
    )
    (net (code "29") (name "Net-(SIMCARD-I{slash}O)") (class "Default")
      (node (ref "SIMCARD") (pin "C7") (pinfunction "I/O_C7") (pintype "bidirectional"))
      (node (ref "TP19") (pin "TP") (pinfunction "TP_TP") (pintype "input"))
      (node (ref "U1") (pin "31") (pinfunction "SIM_DATA_31") (pintype "bidirectional"))
      (node (ref "U5") (pin "P$4") (pinfunction "P$4_P$4") (pintype "bidirectional"))
    )
    (net (code "30") (name "Net-(SIMCARD-RST)") (class "Default")
      (node (ref "SIMCARD") (pin "C2") (pinfunction "RST_C2") (pintype "input"))
      (node (ref "U1") (pin "32") (pinfunction "SIM_CLK_32") (pintype "output"))
      (node (ref "U5") (pin "P$1") (pinfunction "P$1_P$1") (pintype "bidirectional"))
    )
    (net (code "31") (name "Net-(SIMCARD-VCC)") (class "Default")
      (node (ref "C6") (pin "1") (pinfunction "1_1") (pintype "passive"))
      (node (ref "SIMCARD") (pin "C1") (pinfunction "VCC_C1") (pintype "power_in"))
      (node (ref "U1") (pin "30") (pinfunction "SIM_VDD_30") (pintype "power_in"))
      (node (ref "U5") (pin "P$5") (pinfunction "P$5_P$5") (pintype "bidirectional"))
    )
    (net (code "32") (name "Net-(T1-B)") (class "Default")
      (node (ref "R17") (pin "1") (pinfunction "1_1") (pintype "passive"))
      (node (ref "R18") (pin "2") (pinfunction "2_2") (pintype "passive"))
      (node (ref "T1") (pin "1") (pinfunction "B_1") (pintype "passive"))
    )
    (net (code "33") (name "Net-(T2-B)") (class "Default")
      (node (ref "R11") (pin "1") (pinfunction "1_1") (pintype "passive"))
      (node (ref "R12") (pin "2") (pinfunction "2_2") (pintype "passive"))
      (node (ref "T2") (pin "1") (pinfunction "B_1") (pintype "passive"))
    )
    (net (code "34") (name "Net-(U1-BOOT_CFG)") (class "Default")
      (node (ref "TP1") (pin "TP") (pinfunction "TP_TP") (pintype "input"))
      (node (ref "U1") (pin "6") (pinfunction "BOOT_CFG_6") (pintype "input"))
    )
    (net (code "35") (name "Net-(U1-CTS)") (class "Default")
      (node (ref "TP21") (pin "TP") (pinfunction "TP_TP") (pintype "input"))
      (node (ref "U1") (pin "7") (pinfunction "CTS_7") (pintype "output"))
    )
    (net (code "36") (name "Net-(U1-I2C_SCL)") (class "Default")
      (node (ref "TP17") (pin "TP") (pinfunction "TP_TP") (pintype "input"))
      (node (ref "U1") (pin "38") (pinfunction "I2C_SCL_38") (pintype "output"))
    )
    (net (code "37") (name "Net-(U1-I2C_SDA)") (class "Default")
      (node (ref "TP18") (pin "TP") (pinfunction "TP_TP") (pintype "input"))
      (node (ref "U1") (pin "37") (pinfunction "I2C_SDA_37") (pintype "bidirectional"))
    )
    (net (code "38") (name "Net-(U1-NETLIGHT)") (class "Default")
      (node (ref "R28") (pin "2") (pinfunction "2_2") (pintype "passive"))
      (node (ref "U1") (pin "52") (pinfunction "NETLIGHT_52") (pintype "output"))
    )
    (net (code "39") (name "Net-(U1-RTS)") (class "Default")
      (node (ref "TP22") (pin "TP") (pinfunction "TP_TP") (pintype "input"))
      (node (ref "U1") (pin "8") (pinfunction "RTS_8") (pintype "input"))
    )
    (net (code "40") (name "Net-(U1-RXD)") (class "Default")
      (node (ref "TP16") (pin "TP") (pinfunction "TP_TP") (pintype "input"))
      (node (ref "U1") (pin "10") (pinfunction "RXD_10") (pintype "input"))
      (node (ref "U3") (pin "1") (pinfunction "IO/VCC2_1") (pintype "bidirectional"))
    )
    (net (code "41") (name "Net-(U1-STATUS)") (class "Default")
      (node (ref "R33") (pin "2") (pinfunction "2_2") (pintype "passive"))
      (node (ref "U1") (pin "66") (pinfunction "STATUS_66") (pintype "output"))
    )
    (net (code "42") (name "Net-(U1-TXD)") (class "Default")
      (node (ref "TP15") (pin "TP") (pinfunction "TP_TP") (pintype "input"))
      (node (ref "U1") (pin "9") (pinfunction "TXD_9") (pintype "output"))
      (node (ref "U3") (pin "4") (pinfunction "IO/VL2_4") (pintype "bidirectional"))
    )
    (net (code "43") (name "Net-(U1-USB_VBUS)") (class "Default")
      (node (ref "SJ2") (pin "2") (pinfunction "2_2") (pintype "passive"))
      (node (ref "U1") (pin "24") (pinfunction "USB_VBUS_24") (pintype "input"))
    )
    (net (code "44") (name "Net-(U2-DM0)") (class "Default")
      (node (ref "R8") (pin "2") (pinfunction "2_2") (pintype "passive"))
      (node (ref "U2") (pin "2") (pinfunction "DM0_2") (pintype "bidirectional"))
    )
    (net (code "45") (name "Net-(U2-DM2)") (class "Default")
      (node (ref "R19") (pin "2") (pinfunction "2_2") (pintype "passive"))
      (node (ref "U2") (pin "15") (pinfunction "DM2_15") (pintype "bidirectional"))
    )
    (net (code "46") (name "Net-(U2-DM3)") (class "Default")
      (node (ref "R22") (pin "1") (pinfunction "1_1") (pintype "passive"))
      (node (ref "U2") (pin "19") (pinfunction "DM3_19") (pintype "bidirectional"))
    )
    (net (code "47") (name "Net-(U2-DM4)") (class "Default")
      (node (ref "TP24") (pin "TP") (pinfunction "TP_TP") (pintype "input"))
      (node (ref "U2") (pin "23") (pinfunction "DM4_23") (pintype "bidirectional"))
    )
    (net (code "48") (name "Net-(U2-DP0)") (class "Default")
      (node (ref "R25") (pin "1") (pinfunction "1_1") (pintype "passive"))
      (node (ref "R7") (pin "2") (pinfunction "2_2") (pintype "passive"))
      (node (ref "U2") (pin "1") (pinfunction "DP0_1") (pintype "bidirectional"))
    )
    (net (code "49") (name "Net-(U2-DP2)") (class "Default")
      (node (ref "R20") (pin "2") (pinfunction "2_2") (pintype "passive"))
      (node (ref "U2") (pin "16") (pinfunction "DP2_16") (pintype "bidirectional"))
    )
    (net (code "50") (name "Net-(U2-DP3)") (class "Default")
      (node (ref "R21") (pin "1") (pinfunction "1_1") (pintype "passive"))
      (node (ref "U2") (pin "20") (pinfunction "DP3_20") (pintype "bidirectional"))
    )
    (net (code "51") (name "Net-(U2-DP4)") (class "Default")
      (node (ref "TP23") (pin "TP") (pinfunction "TP_TP") (pintype "input"))
      (node (ref "U2") (pin "24") (pinfunction "DP4_24") (pintype "bidirectional"))
    )
    (net (code "52") (name "Net-(U2-~{RESET})") (class "Default")
      (node (ref "TP25") (pin "TP") (pinfunction "TP_TP") (pintype "input"))
      (node (ref "U2") (pin "4") (pinfunction "~{RESET}_4") (pintype "input"))
    )
    (net (code "53") (name "Net-(U3-IO{slash}VCC1)") (class "Default")
      (node (ref "U3") (pin "8") (pinfunction "IO/VCC1_8") (pintype "bidirectional"))
      (node (ref "X1") (pin "2") (pinfunction "S_2") (pintype "passive"))
    )
    (net (code "54") (name "Net-(U3-IO{slash}VL1)") (class "Default")
      (node (ref "U3") (pin "5") (pinfunction "IO/VL1_5") (pintype "bidirectional"))
      (node (ref "X1") (pin "3") (pinfunction "S_3") (pintype "passive"))
    )
    (net (code "55") (name "OUT1") (class "Default")
      (node (ref "U4") (pin "15") (pinfunction "OUT1_15") (pintype "output"))
    )
    (net (code "56") (name "OUT2") (class "Default")
      (node (ref "J1") (pin "1") (pinfunction "1_1") (pintype "passive"))
      (node (ref "TP3") (pin "TP") (pinfunction "TP_TP") (pintype "input"))
      (node (ref "U4") (pin "14") (pinfunction "OUT2_14") (pintype "output"))
    )
    (net (code "57") (name "OUT3") (class "Default")
      (node (ref "J1") (pin "5") (pinfunction "5_5") (pintype "passive"))
      (node (ref "TP4") (pin "TP") (pinfunction "TP_TP") (pintype "input"))
      (node (ref "U4") (pin "11") (pinfunction "OUT3_11") (pintype "output"))
    )
    (net (code "58") (name "OUT4") (class "Default")
      (node (ref "U4") (pin "10") (pinfunction "NC_10") (pintype "passive"))
    )
    (net (code "59") (name "OVRCUR1") (class "Default")
      (node (ref "U2") (pin "10") (pinfunction "~{OVRCUR1}_10") (pintype "output"))
      (node (ref "U4") (pin "16") (pinfunction "~{OC1}_16") (pintype "output"))
    )
    (net (code "60") (name "OVRCUR2") (class "Default")
      (node (ref "U2") (pin "14") (pinfunction "~{OVRCUR2}_14") (pintype "output"))
      (node (ref "U4") (pin "13") (pinfunction "~{OC2}_13") (pintype "output"))
    )
    (net (code "61") (name "OVRCUR3") (class "Default")
      (node (ref "U2") (pin "18") (pinfunction "~{OVRCUR3}_18") (pintype "output"))
      (node (ref "U4") (pin "12") (pinfunction "~{OC3}_12") (pintype "output"))
    )
    (net (code "62") (name "OVRCUR4") (class "Default")
      (node (ref "U2") (pin "22") (pinfunction "~{OVRCUR4}_22") (pintype "input"))
      (node (ref "U4") (pin "9") (pinfunction "NC_3_9") (pintype "passive"))
    )
    (net (code "63") (name "PB2") (class "Default")
      (node (ref "R14") (pin "2") (pinfunction "2_2") (pintype "passive"))
      (node (ref "SV2") (pin "17") (pinfunction "17_17") (pintype "passive"))
      (node (ref "SW2") (pin "P$1") (pinfunction "P$1_P$1") (pintype "passive"))
    )
    (net (code "64") (name "PB3") (class "Default")
      (node (ref "R16") (pin "2") (pinfunction "2_2") (pintype "passive"))
      (node (ref "SV2") (pin "19") (pinfunction "19_19") (pintype "passive"))
      (node (ref "SW3") (pin "P$1") (pinfunction "P$1_P$1") (pintype "passive"))
    )
    (net (code "65") (name "PRE_ANT") (class "Default")
      (node (ref "C15") (pin "1") (pinfunction "1_1") (pintype "passive"))
      (node (ref "R26") (pin "2") (pinfunction "2_2") (pintype "passive"))
      (node (ref "U1") (pin "60") (pinfunction "RF_ANT_60") (pintype "bidirectional"))
    )
    (net (code "66") (name "PRE_GPS") (class "Default")
      (node (ref "C16") (pin "2") (pinfunction "2_2") (pintype "passive"))
      (node (ref "TP2") (pin "TP") (pinfunction "TP_TP") (pintype "input"))
      (node (ref "U1") (pin "53") (pinfunction "GNSS_ANT_53") (pintype "input"))
    )
    (net (code "67") (name "PWRKEY") (class "Default")
      (node (ref "C8") (pin "1") (pinfunction "1_1") (pintype "passive"))
      (node (ref "SV2") (pin "3") (pinfunction "3_3") (pintype "passive"))
      (node (ref "T1") (pin "3") (pinfunction "C_3") (pintype "passive"))
      (node (ref "U1") (pin "1") (pinfunction "~{PWRKEY}_1") (pintype "input"))
    )
    (net (code "68") (name "PWRON1") (class "Default")
      (node (ref "U2") (pin "9") (pinfunction "~{PWRON1}_9") (pintype "output"))
      (node (ref "U4") (pin "3") (pinfunction "~{EN1}_3") (pintype "input"))
    )
    (net (code "69") (name "PWRON2") (class "Default")
      (node (ref "U2") (pin "13") (pinfunction "~{PWRON2}_13") (pintype "output"))
      (node (ref "U4") (pin "4") (pinfunction "~{EN2}_4") (pintype "input"))
    )
    (net (code "70") (name "PWRON3") (class "Default")
      (node (ref "U2") (pin "17") (pinfunction "~{PWRON3}_17") (pintype "output"))
      (node (ref "U4") (pin "7") (pinfunction "~{EN3}_7") (pintype "input"))
    )
    (net (code "71") (name "PWRON4") (class "Default")
      (node (ref "U2") (pin "21") (pinfunction "~{PWRON4}_21") (pintype "output"))
      (node (ref "U4") (pin "8") (pinfunction "NC_2_8") (pintype "passive"))
    )
    (net (code "72") (name "REGULATED") (class "Default")
      (node (ref "POWER_SUPPLY") (pin "4") (pinfunction "OUT_4") (pintype "bidirectional"))
      (node (ref "R5") (pin "2") (pinfunction "2_2") (pintype "passive"))
      (node (ref "R6") (pin "2") (pinfunction "2_2") (pintype "passive"))
      (node (ref "SJ1") (pin "3") (pinfunction "3_3") (pintype "passive"))
    )
    (net (code "73") (name "SLEEP") (class "Default")
      (node (ref "R12") (pin "1") (pinfunction "1_1") (pintype "passive"))
      (node (ref "SV2") (pin "2") (pinfunction "2_2") (pintype "passive"))
    )
    (net (code "74") (name "USB1_D+") (class "Default")
      (node (ref "J1") (pin "3") (pinfunction "3_3") (pintype "passive"))
      (node (ref "R20") (pin "1") (pinfunction "1_1") (pintype "passive"))
      (node (ref "R24") (pin "2") (pinfunction "2_2") (pintype "passive"))
      (node (ref "TP8") (pin "TP") (pinfunction "TP_TP") (pintype "input"))
    )
    (net (code "75") (name "USB1_D-") (class "Default")
      (node (ref "J1") (pin "2") (pinfunction "2_2") (pintype "passive"))
      (node (ref "R19") (pin "1") (pinfunction "1_1") (pintype "passive"))
      (node (ref "R23") (pin "2") (pinfunction "2_2") (pintype "passive"))
      (node (ref "TP7") (pin "TP") (pinfunction "TP_TP") (pintype "input"))
    )
    (net (code "76") (name "USB2_D+") (class "Default")
      (node (ref "J1") (pin "7") (pinfunction "7_7") (pintype "passive"))
      (node (ref "R13") (pin "2") (pinfunction "2_2") (pintype "passive"))
      (node (ref "R21") (pin "2") (pinfunction "2_2") (pintype "passive"))
      (node (ref "TP10") (pin "TP") (pinfunction "TP_TP") (pintype "input"))
    )
    (net (code "77") (name "USB2_D-") (class "Default")
      (node (ref "J1") (pin "6") (pinfunction "6_6") (pintype "passive"))
      (node (ref "R15") (pin "2") (pinfunction "2_2") (pintype "passive"))
      (node (ref "R22") (pin "2") (pinfunction "2_2") (pintype "passive"))
      (node (ref "TP9") (pin "TP") (pinfunction "TP_TP") (pintype "input"))
    )
    (net (code "78") (name "VDD_EXT") (class "Default")
      (node (ref "T2") (pin "3") (pinfunction "C_3") (pintype "passive"))
      (node (ref "U1") (pin "3") (pinfunction "DTR_3") (pintype "input"))
    )
    (net (code "79") (name "VPP") (class "Default")
      (node (ref "SIMCARD") (pin "C6") (pinfunction "VPP_C6") (pintype "power_in"))
    )
    (net (code "80") (name "XTAL1") (class "Default")
      (node (ref "C12") (pin "1") (pinfunction "1_1") (pintype "passive"))
      (node (ref "CR1") (pin "1") (pinfunction "1_1") (pintype "passive"))
      (node (ref "U2") (pin "30") (pinfunction "XTAL1_30") (pintype "input"))
    )
    (net (code "81") (name "XTAL2") (class "Default")
      (node (ref "R9") (pin "2") (pinfunction "2_2") (pintype "passive"))
      (node (ref "U2") (pin "29") (pinfunction "XTAL2_29") (pintype "output"))
    )
    (net (code "82") (name "unconnected-(POWER_SUPPLY-TAB-Pad6)") (class "Default")
      (node (ref "POWER_SUPPLY") (pin "6") (pinfunction "TAB_6") (pintype "bidirectional"))
    )
    (net (code "83") (name "unconnected-(SV1-Pad1)") (class "Default")
      (node (ref "SV1") (pin "1") (pinfunction "1_1") (pintype "passive"))
    )
    (net (code "84") (name "unconnected-(SV1-Pad2)") (class "Default")
      (node (ref "SV1") (pin "2") (pinfunction "2_2") (pintype "passive"))
    )
    (net (code "85") (name "unconnected-(SV1-Pad3)") (class "Default")
      (node (ref "SV1") (pin "3") (pinfunction "3_3") (pintype "passive"))
    )
    (net (code "86") (name "unconnected-(SV1-Pad4)") (class "Default")
      (node (ref "SV1") (pin "4") (pinfunction "4_4") (pintype "passive"))
    )
    (net (code "87") (name "unconnected-(SV1-Pad5)") (class "Default")
      (node (ref "SV1") (pin "5") (pinfunction "5_5") (pintype "passive"))
    )
    (net (code "88") (name "unconnected-(SV1-Pad6)") (class "Default")
      (node (ref "SV1") (pin "6") (pinfunction "6_6") (pintype "passive"))
    )
    (net (code "89") (name "unconnected-(SV1-Pad7)") (class "Default")
      (node (ref "SV1") (pin "7") (pinfunction "7_7") (pintype "passive"))
    )
    (net (code "90") (name "unconnected-(SV1-Pad8)") (class "Default")
      (node (ref "SV1") (pin "8") (pinfunction "8_8") (pintype "passive"))
    )
    (net (code "91") (name "unconnected-(SV1-Pad10)") (class "Default")
      (node (ref "SV1") (pin "10") (pinfunction "10_10") (pintype "passive"))
    )
    (net (code "92") (name "unconnected-(SV1-Pad12)") (class "Default")
      (node (ref "SV1") (pin "12") (pinfunction "12_12") (pintype "passive"))
    )
    (net (code "93") (name "unconnected-(SV1-Pad13)") (class "Default")
      (node (ref "SV1") (pin "13") (pinfunction "13_13") (pintype "passive"))
    )
    (net (code "94") (name "unconnected-(SV1-Pad16)") (class "Default")
      (node (ref "SV1") (pin "16") (pinfunction "16_16") (pintype "passive"))
    )
    (net (code "95") (name "unconnected-(SV1-Pad17)") (class "Default")
      (node (ref "SV1") (pin "17") (pinfunction "17_17") (pintype "passive"))
    )
    (net (code "96") (name "unconnected-(SV1-Pad18)") (class "Default")
      (node (ref "SV1") (pin "18") (pinfunction "18_18") (pintype "passive"))
    )
    (net (code "97") (name "unconnected-(SV1-Pad19)") (class "Default")
      (node (ref "SV1") (pin "19") (pinfunction "19_19") (pintype "passive"))
    )
    (net (code "98") (name "unconnected-(SV1-Pad20)") (class "Default")
      (node (ref "SV1") (pin "20") (pinfunction "20_20") (pintype "passive"))
    )
    (net (code "99") (name "unconnected-(SV1-Pad21)") (class "Default")
      (node (ref "SV1") (pin "21") (pinfunction "21_21") (pintype "passive"))
    )
    (net (code "100") (name "unconnected-(SV1-Pad22)") (class "Default")
      (node (ref "SV1") (pin "22") (pinfunction "22_22") (pintype "passive"))
    )
    (net (code "101") (name "unconnected-(SV1-Pad23)") (class "Default")
      (node (ref "SV1") (pin "23") (pinfunction "23_23") (pintype "passive"))
    )
    (net (code "102") (name "unconnected-(SV1-Pad25)") (class "Default")
      (node (ref "SV1") (pin "25") (pinfunction "25_25") (pintype "passive"))
    )
    (net (code "103") (name "unconnected-(SV1-Pad27)") (class "Default")
      (node (ref "SV1") (pin "27") (pinfunction "27_27") (pintype "passive"))
    )
    (net (code "104") (name "unconnected-(SV1-Pad29)") (class "Default")
      (node (ref "SV1") (pin "29") (pinfunction "29_29") (pintype "passive"))
    )
    (net (code "105") (name "unconnected-(SV1-Pad30)") (class "Default")
      (node (ref "SV1") (pin "30") (pinfunction "30_30") (pintype "passive"))
    )
    (net (code "106") (name "unconnected-(SV1-Pad31)") (class "Default")
      (node (ref "SV1") (pin "31") (pinfunction "31_31") (pintype "passive"))
    )
    (net (code "107") (name "unconnected-(SV1-Pad32)") (class "Default")
      (node (ref "SV1") (pin "32") (pinfunction "32_32") (pintype "passive"))
    )
    (net (code "108") (name "unconnected-(SV1-Pad33)") (class "Default")
      (node (ref "SV1") (pin "33") (pinfunction "33_33") (pintype "passive"))
    )
    (net (code "109") (name "unconnected-(SV1-Pad34)") (class "Default")
      (node (ref "SV1") (pin "34") (pinfunction "34_34") (pintype "passive"))
    )
    (net (code "110") (name "unconnected-(SV1-Pad35)") (class "Default")
      (node (ref "SV1") (pin "35") (pinfunction "35_35") (pintype "passive"))
    )
    (net (code "111") (name "unconnected-(SV1-Pad36)") (class "Default")
      (node (ref "SV1") (pin "36") (pinfunction "36_36") (pintype "passive"))
    )
    (net (code "112") (name "unconnected-(SV2-Pad1)") (class "Default")
      (node (ref "SV2") (pin "1") (pinfunction "1_1") (pintype "passive"))
    )
    (net (code "113") (name "unconnected-(SV2-Pad4)") (class "Default")
      (node (ref "SV2") (pin "4") (pinfunction "4_4") (pintype "passive"))
    )
    (net (code "114") (name "unconnected-(SV2-Pad5)") (class "Default")
      (node (ref "SV2") (pin "5") (pinfunction "5_5") (pintype "passive"))
    )
    (net (code "115") (name "unconnected-(SV2-Pad7)") (class "Default")
      (node (ref "SV2") (pin "7") (pinfunction "7_7") (pintype "passive"))
    )
    (net (code "116") (name "unconnected-(SV2-Pad12)") (class "Default")
      (node (ref "SV2") (pin "12") (pinfunction "12_12") (pintype "passive"))
    )
    (net (code "117") (name "unconnected-(SV2-Pad13)") (class "Default")
      (node (ref "SV2") (pin "13") (pinfunction "13_13") (pintype "passive"))
    )
    (net (code "118") (name "unconnected-(SV2-Pad14)") (class "Default")
      (node (ref "SV2") (pin "14") (pinfunction "14_14") (pintype "passive"))
    )
    (net (code "119") (name "unconnected-(SV2-Pad16)") (class "Default")
      (node (ref "SV2") (pin "16") (pinfunction "16_16") (pintype "passive"))
    )
    (net (code "120") (name "unconnected-(SV2-Pad18)") (class "Default")
      (node (ref "SV2") (pin "18") (pinfunction "18_18") (pintype "passive"))
    )
    (net (code "121") (name "unconnected-(SV2-Pad20)") (class "Default")
      (node (ref "SV2") (pin "20") (pinfunction "20_20") (pintype "passive"))
    )
    (net (code "122") (name "unconnected-(SV2-Pad21)") (class "Default")
      (node (ref "SV2") (pin "21") (pinfunction "21_21") (pintype "passive"))
    )
    (net (code "123") (name "unconnected-(SV2-Pad22)") (class "Default")
      (node (ref "SV2") (pin "22") (pinfunction "22_22") (pintype "passive"))
    )
    (net (code "124") (name "unconnected-(SV2-Pad23)") (class "Default")
      (node (ref "SV2") (pin "23") (pinfunction "23_23") (pintype "passive"))
    )
    (net (code "125") (name "unconnected-(SV2-Pad24)") (class "Default")
      (node (ref "SV2") (pin "24") (pinfunction "24_24") (pintype "passive"))
    )
    (net (code "126") (name "unconnected-(SV2-Pad25)") (class "Default")
      (node (ref "SV2") (pin "25") (pinfunction "25_25") (pintype "passive"))
    )
    (net (code "127") (name "unconnected-(SV2-Pad26)") (class "Default")
      (node (ref "SV2") (pin "26") (pinfunction "26_26") (pintype "passive"))
    )
    (net (code "128") (name "unconnected-(SV2-Pad27)") (class "Default")
      (node (ref "SV2") (pin "27") (pinfunction "27_27") (pintype "passive"))
    )
    (net (code "129") (name "unconnected-(SV2-Pad28)") (class "Default")
      (node (ref "SV2") (pin "28") (pinfunction "28_28") (pintype "passive"))
    )
    (net (code "130") (name "unconnected-(SV2-Pad29)") (class "Default")
      (node (ref "SV2") (pin "29") (pinfunction "29_29") (pintype "passive"))
    )
    (net (code "131") (name "unconnected-(SV2-Pad30)") (class "Default")
      (node (ref "SV2") (pin "30") (pinfunction "30_30") (pintype "passive"))
    )
    (net (code "132") (name "unconnected-(SV2-Pad31)") (class "Default")
      (node (ref "SV2") (pin "31") (pinfunction "31_31") (pintype "passive"))
    )
    (net (code "133") (name "unconnected-(SV2-Pad32)") (class "Default")
      (node (ref "SV2") (pin "32") (pinfunction "32_32") (pintype "passive"))
    )
    (net (code "134") (name "unconnected-(SV2-Pad33)") (class "Default")
      (node (ref "SV2") (pin "33") (pinfunction "33_33") (pintype "passive"))
    )
    (net (code "135") (name "unconnected-(SV2-Pad34)") (class "Default")
      (node (ref "SV2") (pin "34") (pinfunction "34_34") (pintype "passive"))
    )
    (net (code "136") (name "unconnected-(SV2-Pad35)") (class "Default")
      (node (ref "SV2") (pin "35") (pinfunction "35_35") (pintype "passive"))
    )
    (net (code "137") (name "unconnected-(SV2-Pad36)") (class "Default")
      (node (ref "SV2") (pin "36") (pinfunction "36_36") (pintype "passive"))
    )
    (net (code "138") (name "unconnected-(U1-ADC-Pad25)") (class "Default")
      (node (ref "U1") (pin "25") (pinfunction "ADC_25") (pintype "input"))
    )
    (net (code "139") (name "unconnected-(U1-DCD-Pad5)") (class "Default")
      (node (ref "U1") (pin "5") (pinfunction "DCD_5") (pintype "output"))
    )
    (net (code "140") (name "unconnected-(U1-GPIO0-Pad50)") (class "Default")
      (node (ref "U1") (pin "50") (pinfunction "GPIO0_50") (pintype "bidirectional"))
    )
    (net (code "141") (name "unconnected-(U1-GPIO1-Pad49)") (class "Default")
      (node (ref "U1") (pin "49") (pinfunction "GPIO1_49") (pintype "bidirectional"))
    )
    (net (code "142") (name "unconnected-(U1-GPIO2-Pad67)") (class "Default")
      (node (ref "U1") (pin "67") (pinfunction "GPIO2_67") (pintype "bidirectional"))
    )
    (net (code "143") (name "unconnected-(U1-GPIO3-Pad68)") (class "Default")
      (node (ref "U1") (pin "68") (pinfunction "GPIO3_68") (pintype "bidirectional"))
    )
    (net (code "144") (name "unconnected-(U1-GPIO4-Pad48)") (class "Default")
      (node (ref "U1") (pin "48") (pinfunction "GPIO4_48") (pintype "bidirectional"))
    )
    (net (code "145") (name "unconnected-(U1-MDM_LOG_TX-Pad23)") (class "Default")
      (node (ref "U1") (pin "23") (pinfunction "MDM_LOG_TX_23") (pintype "output"))
    )
    (net (code "146") (name "unconnected-(U1-PCM_CLK-Pad11)") (class "Default")
      (node (ref "U1") (pin "11") (pinfunction "PCM_CLK_11") (pintype "output"))
    )
    (net (code "147") (name "unconnected-(U1-PCM_DIN-Pad13)") (class "Default")
      (node (ref "U1") (pin "13") (pinfunction "PCM_DIN_13") (pintype "input"))
    )
    (net (code "148") (name "unconnected-(U1-PCM_DOUT-Pad14)") (class "Default")
      (node (ref "U1") (pin "14") (pinfunction "PCM_DOUT_14") (pintype "output"))
    )
    (net (code "149") (name "unconnected-(U1-PCM_SYNC-Pad12)") (class "Default")
      (node (ref "U1") (pin "12") (pinfunction "PCM_SYNC_12") (pintype "output"))
    )
    (net (code "150") (name "unconnected-(U1-RI-Pad4)") (class "Default")
      (node (ref "U1") (pin "4") (pinfunction "RI_4") (pintype "output"))
    )
    (net (code "151") (name "unconnected-(U1-SIM_DET-Pad34)") (class "Default")
      (node (ref "U1") (pin "34") (pinfunction "SIM_DET_34") (pintype "input"))
    )
    (net (code "152") (name "unconnected-(U2-EECLK-Pad5)") (class "Default")
      (node (ref "U2") (pin "5") (pinfunction "EECLK_5") (pintype "output"))
    )
    (net (code "153") (name "unconnected-(U2-SUSPND-Pad32)") (class "Default")
      (node (ref "U2") (pin "32") (pinfunction "SUSPND_32") (pintype "output"))
    )
  )
)
